# super_micro.net
KiCad netlist of a schematic drawn in EAGLE
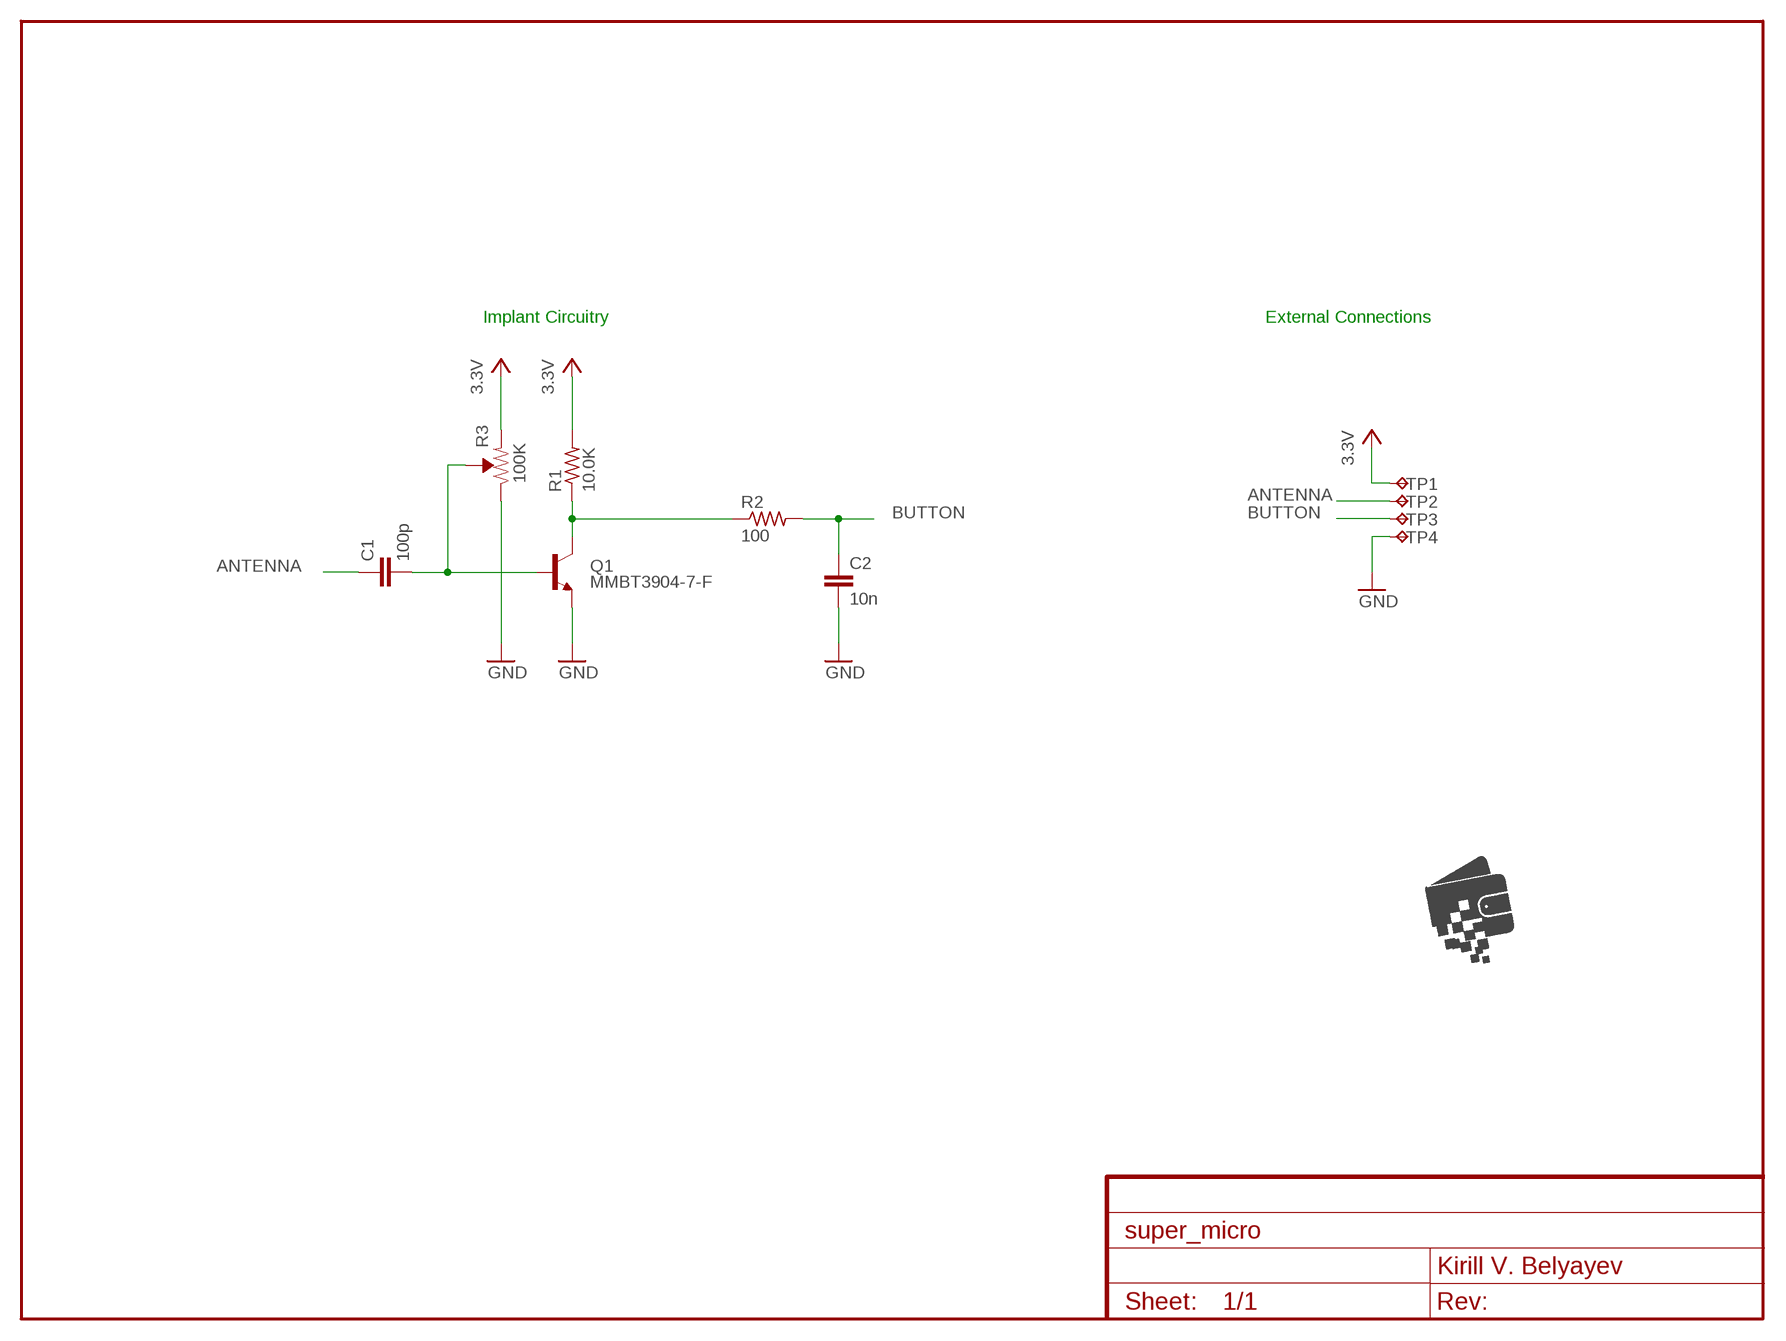
[diagram p0: schematic, sheet 1]

(export (version "E")
  (design (tool "Eeschema 10.0.6"))
  (components
    (comp (ref "C1")
      (value "100p")
      (footprint "eagle-import:C0603")
      (libsource (lib "eagle-import") (part "C-EUC0603"))
    )
    (comp (ref "C2")
      (value "10n")
      (footprint "eagle-import:C0603")
      (libsource (lib "eagle-import") (part "C-EUC0603"))
    )
    (comp (ref "LOGO1")
      (value "WF_LOGO_S")
      (footprint "eagle-import:WF_LOGO_S")
      (libsource (lib "eagle-import") (part "WF_LOGO_S"))
    )
    (comp (ref "Q1")
      (value "MMBT3904-7-F")
      (footprint "eagle-import:SOT-23")
      (fields (field (name "MANUFACTURER") "Diodes Inc."))
      (libsource (lib "eagle-import") (part "MMBT3904-7-F"))
    )
    (comp (ref "R1")
      (value "10.0K")
      (footprint "eagle-import:R0603")
      (libsource (lib "eagle-import") (part "R-US_R0603"))
    )
    (comp (ref "R2")
      (value "100")
      (footprint "eagle-import:R0603")
      (libsource (lib "eagle-import") (part "R-US_R0603"))
    )
    (comp (ref "R3")
      (value "100K")
      (footprint "eagle-import:3312J")
      (fields (field (name "MAN-PART_NUM") "3312J-1-104E") (field (name "MANUFACTURER") "Bourns Inc."))
      (libsource (lib "eagle-import") (part "3312J-1-104E"))
    )
    (comp (ref "TP1")
      (value "TEST-POINT40MIL")
      (footprint "eagle-import:TEST-POINT-40MILL")
      (libsource (lib "eagle-import") (part "TEST-POINT40MIL"))
    )
    (comp (ref "TP2")
      (value "TEST-POINT40MIL")
      (footprint "eagle-import:TEST-POINT-40MILL")
      (libsource (lib "eagle-import") (part "TEST-POINT40MIL"))
    )
    (comp (ref "TP3")
      (value "TEST-POINT40MIL")
      (footprint "eagle-import:TEST-POINT-40MILL")
      (libsource (lib "eagle-import") (part "TEST-POINT40MIL"))
    )
    (comp (ref "TP4")
      (value "TEST-POINT40MIL")
      (footprint "eagle-import:TEST-POINT-40MILL")
      (libsource (lib "eagle-import") (part "TEST-POINT40MIL"))
    )
  )
  (nets
    (net (code "1") (name "/ANTENNA") (class "Default")
      (node (ref "C1") (pin "1") (pinfunction "1_1") (pintype "passive"))
      (node (ref "TP2") (pin "1") (pinfunction "PP_1") (pintype "input"))
    )
    (net (code "2") (name "/BUTTON") (class "Default")
      (node (ref "C2") (pin "1") (pinfunction "1_1") (pintype "passive"))
      (node (ref "R2") (pin "2") (pinfunction "2_2") (pintype "passive"))
      (node (ref "TP3") (pin "1") (pinfunction "PP_1") (pintype "input"))
    )
    (net (code "3") (name "3.3V") (class "Default")
      (node (ref "R1") (pin "2") (pinfunction "2_2") (pintype "passive"))
      (node (ref "R3") (pin "3") (pinfunction "3_3") (pintype "passive"))
      (node (ref "TP1") (pin "1") (pinfunction "PP_1") (pintype "input"))
    )
    (net (code "4") (name "GND") (class "Default")
      (node (ref "C2") (pin "2") (pinfunction "2_2") (pintype "passive"))
      (node (ref "Q1") (pin "2") (pinfunction "E_2") (pintype "passive"))
      (node (ref "R3") (pin "1") (pinfunction "1_1") (pintype "passive"))
      (node (ref "TP4") (pin "1") (pinfunction "PP_1") (pintype "input"))
    )
    (net (code "5") (name "Net-(Q1-B)") (class "Default")
      (node (ref "C1") (pin "2") (pinfunction "2_2") (pintype "passive"))
      (node (ref "Q1") (pin "1") (pinfunction "B_1") (pintype "passive"))
      (node (ref "R3") (pin "2") (pinfunction "2_2") (pintype "passive"))
    )
    (net (code "6") (name "Net-(Q1-C)") (class "Default")
      (node (ref "Q1") (pin "3") (pinfunction "C_3") (pintype "passive"))
      (node (ref "R1") (pin "1") (pinfunction "1_1") (pintype "passive"))
      (node (ref "R2") (pin "1") (pinfunction "1_1") (pintype "passive"))
    )
  )
)
